# TDA5051A_DC_LC_PLCModem.net
KiCad netlist of a schematic drawn in EAGLE
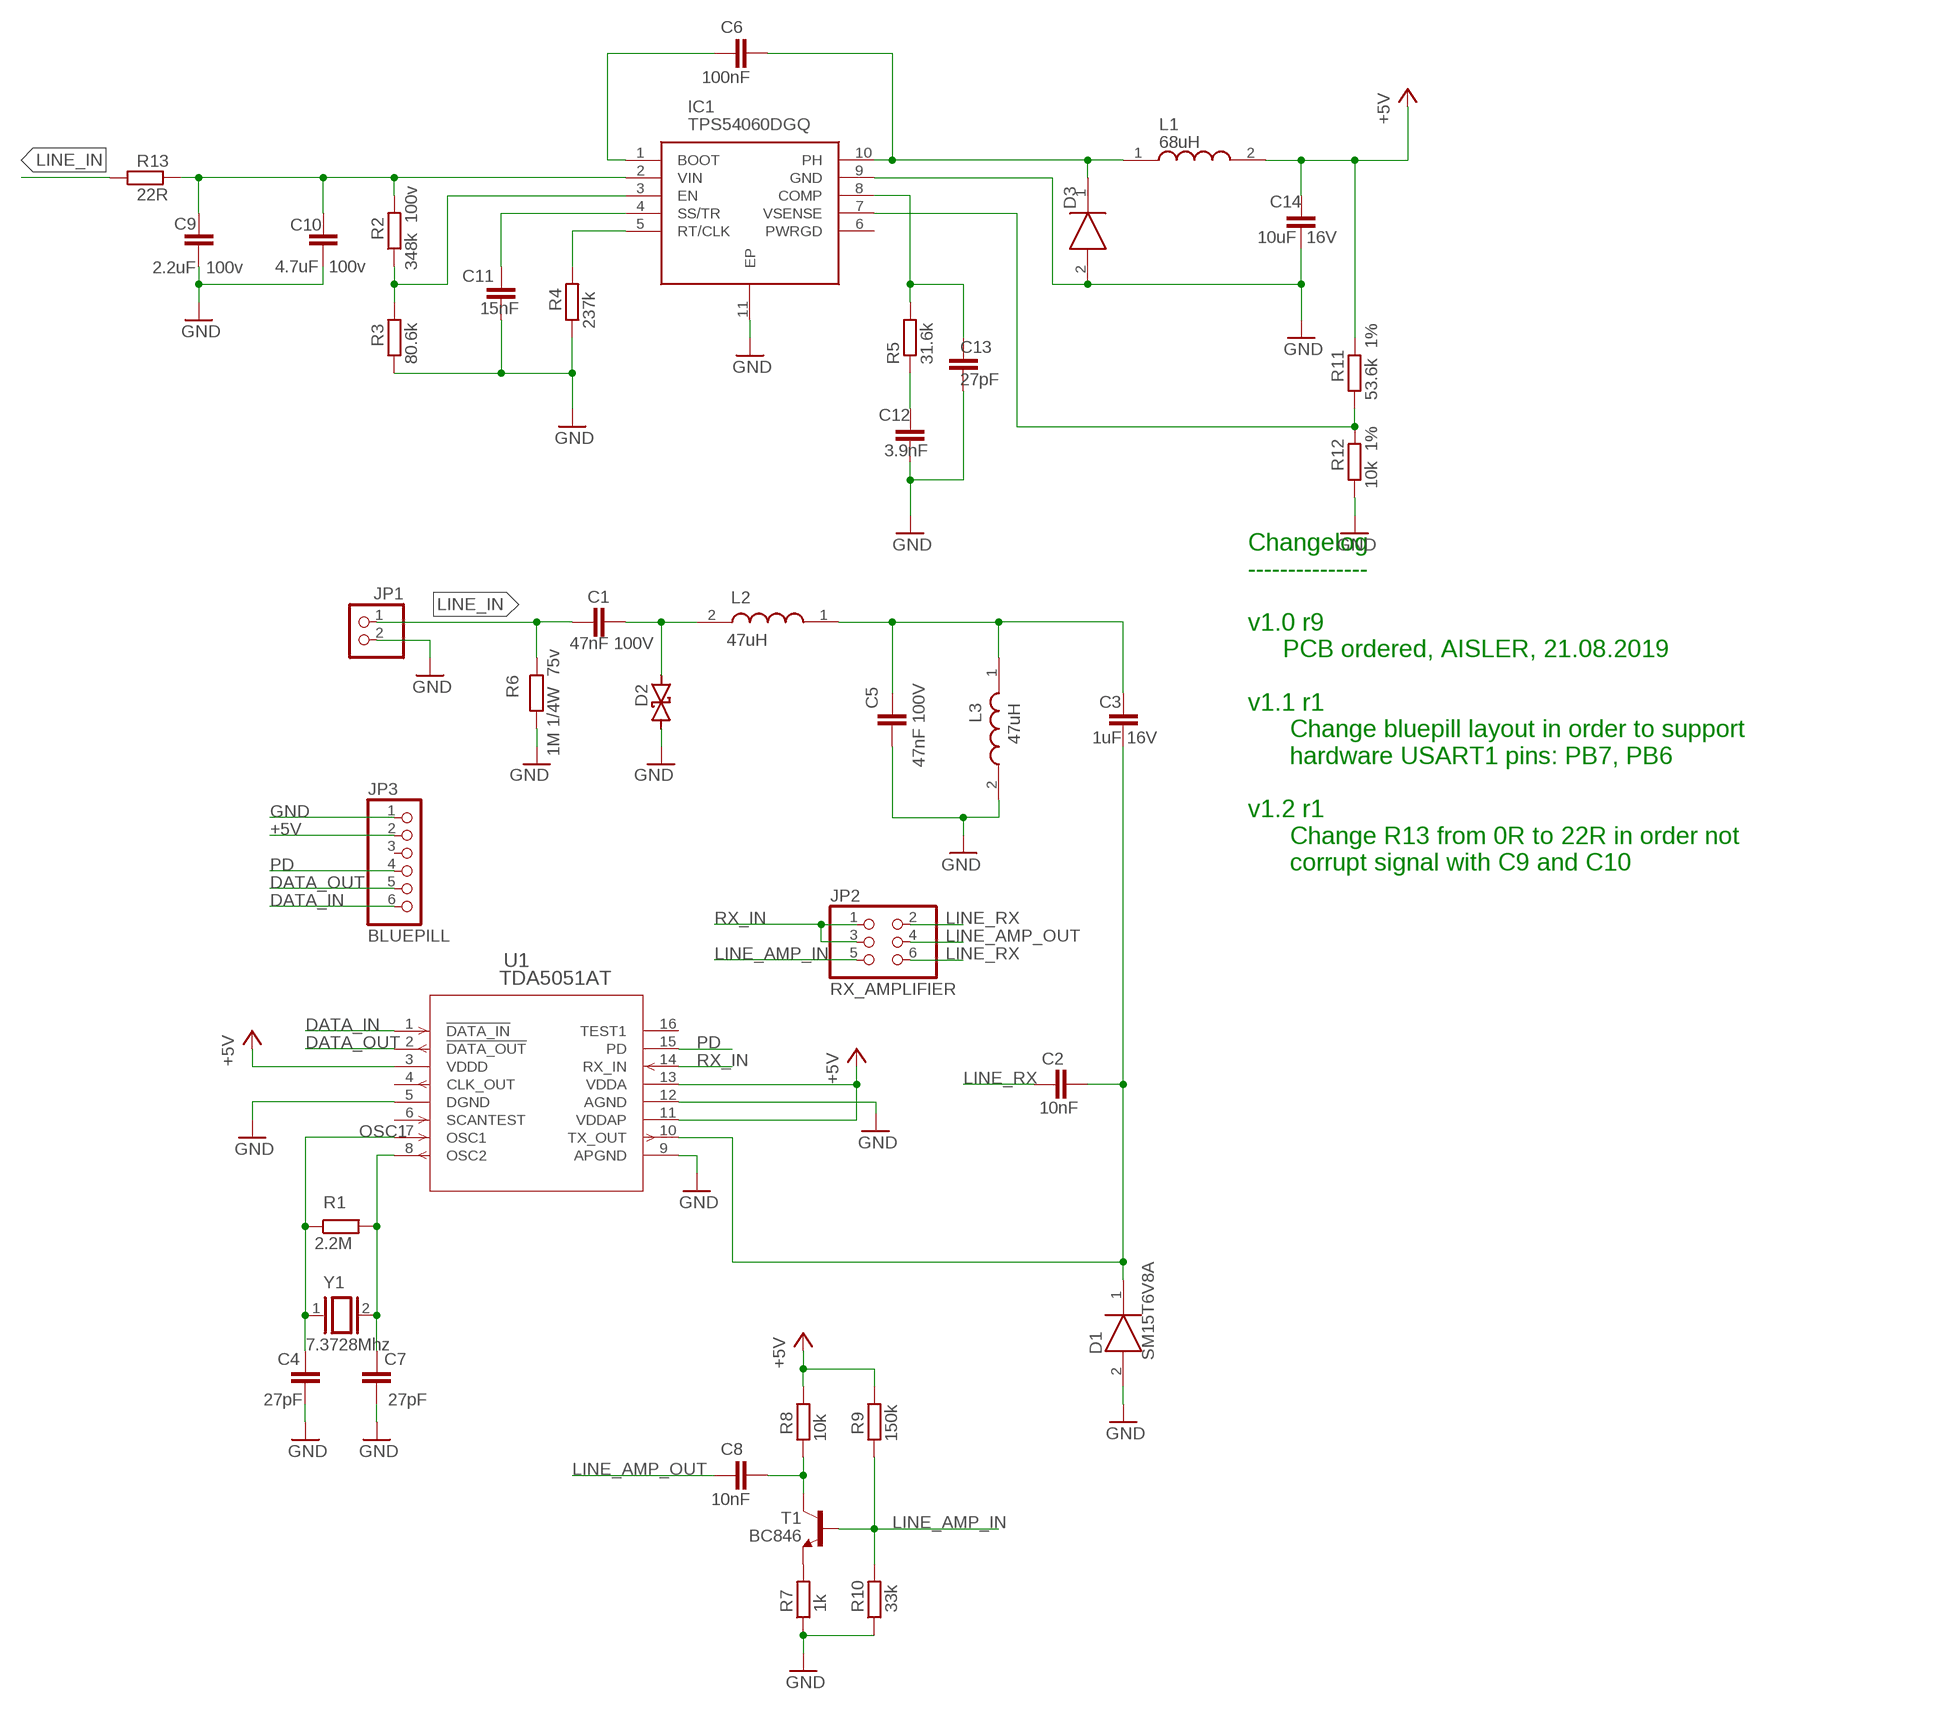
[diagram p0: schematic, sheet 1]

(export (version "E")
  (design (tool "Eeschema 10.0.6"))
  (components
    (comp (ref "C1")
      (value "47nF 100V")
      (footprint "eagle-import:C1206")
      (fields (field (name "MF") "KEMET") (field (name "MPN") "C1206C473K1RACAUTO"))
      (libsource (lib "eagle-import") (part "C-EUC1206"))
    )
    (comp (ref "C2")
      (value "10nF")
      (footprint "eagle-import:C0603")
      (fields (field (name "MF") "KEMET") (field (name "MPN") "C0603C103K5RACAUTO7411"))
      (libsource (lib "eagle-import") (part "C-EUC0603"))
    )
    (comp (ref "C3")
      (value "1uF 16V")
      (footprint "eagle-import:C0805")
      (fields (field (name "MF") "KEMET") (field (name "MPN") "C0805C105K4RACAUTO"))
      (libsource (lib "eagle-import") (part "C-EUC0805"))
    )
    (comp (ref "C4")
      (value "27pF")
      (footprint "eagle-import:C0603")
      (fields (field (name "MF") "AVX") (field (name "MPN") "06035A270JAT2A"))
      (libsource (lib "eagle-import") (part "C-EUC0603"))
    )
    (comp (ref "C5")
      (value "47nF 100V")
      (footprint "eagle-import:C1206")
      (fields (field (name "MF") "KEMET") (field (name "MPN") "C1206C473K1RACAUTO"))
      (libsource (lib "eagle-import") (part "C-EUC1206"))
    )
    (comp (ref "C6")
      (value "100nF")
      (footprint "eagle-import:C0603")
      (fields (field (name "MF") "KEMET") (field (name "MPN") "C0603C104K5RECAUTO"))
      (libsource (lib "eagle-import") (part "C-EUC0603"))
    )
    (comp (ref "C7")
      (value "27pF")
      (footprint "eagle-import:C0603")
      (fields (field (name "MF") "AVX") (field (name "MPN") "06035A270JAT2A"))
      (libsource (lib "eagle-import") (part "C-EUC0603"))
    )
    (comp (ref "C8")
      (value "10nF")
      (footprint "eagle-import:C0603")
      (fields (field (name "MF") "KEMET") (field (name "MPN") "C0603C103K5RACAUTO7411"))
      (libsource (lib "eagle-import") (part "C-EUC0603"))
    )
    (comp (ref "C9")
      (value "2.2uF 100v")
      (footprint "eagle-import:C1210")
      (fields (field (name "MF") "TDK") (field (name "MPN") "C3225X7R2A225K230AB"))
      (libsource (lib "eagle-import") (part "C-EUC1210"))
    )
    (comp (ref "C10")
      (value "4.7uF 100v")
      (footprint "eagle-import:C1210")
      (fields (field (name "MF") "TDK") (field (name "MPN") "CGA6M3X7S2A475K200AB"))
      (libsource (lib "eagle-import") (part "C-EUC1210"))
    )
    (comp (ref "C11")
      (value "15nF")
      (footprint "eagle-import:C0603")
      (fields (field (name "MF") "AVX") (field (name "MPN") "06035C153KAT2A"))
      (libsource (lib "eagle-import") (part "C-EUC0603"))
    )
    (comp (ref "C12")
      (value "3.9nF")
      (footprint "eagle-import:C0603")
      (fields (field (name "MF") "Murata Electronics") (field (name "MPN") "GCM1885C1H392JA16D"))
      (libsource (lib "eagle-import") (part "C-EUC0603"))
    )
    (comp (ref "C13")
      (value "27pF")
      (footprint "eagle-import:C0603")
      (fields (field (name "MF") "AVX") (field (name "MPN") "06035A270JAT2A"))
      (libsource (lib "eagle-import") (part "C-EUC0603"))
    )
    (comp (ref "C14")
      (value "10uF 16V")
      (footprint "eagle-import:C0603")
      (fields (field (name "MF") "Murata Electronics") (field (name "MPN") "GRM188R61C106KAALD"))
      (libsource (lib "eagle-import") (part "C-EUC0603"))
    )
    (comp (ref "D1")
      (value "SM15T6V8A")
      (footprint "eagle-import:DIOM8059X265N")
      (fields (field (name "MOUSER_PART_NUMBER") "511-SM15T6V8A") (field (name "MF") "STMicroelectronics"))
      (libsource (lib "eagle-import") (part "SM15T6V8A"))
    )
    (comp (ref "D2")
      (value "SM15T6V8CA")
      (footprint "eagle-import:DIOM8059X265N")
      (fields (field (name "MOUSER_PART_NUMBER") "511-SM15T6V8CA") (field (name "MF") "STMicroelectronics"))
      (libsource (lib "eagle-import") (part "SM15T6V8CA"))
    )
    (comp (ref "D3")
      (value "STPS2H100A")
      (footprint "eagle-import:DIOM5126X265N")
      (fields (field (name "MOUSER_PART_NUMBER") "511-STPS2H100A") (field (name "MF") "STMicroelectronics"))
      (libsource (lib "eagle-import") (part "STPS2H100A"))
    )
    (comp (ref "IC1")
      (value "TPS54060DGQ")
      (footprint "eagle-import:SOP50P490X110-11N")
      (fields
        (field (name "MOUSER_PART_NUMBER") "595-TPS54060DGQ")
        (field (name "MF") "Texas Instruments")
        (field (name "MPN") "TPS54060DGQR")
      )
      (libsource (lib "eagle-import") (part "TPS54060DGQ"))
    )
    (comp (ref "JP1")
      (value "PINHD-1X2")
      (footprint "eagle-import:1X02")
      (libsource (lib "eagle-import") (part "PINHD-1X2"))
    )
    (comp (ref "JP2")
      (value "RX_AMPLIFIER")
      (footprint "eagle-import:2X03")
      (libsource (lib "eagle-import") (part "PINHD-2X3"))
    )
    (comp (ref "JP3")
      (value "BLUEPILL")
      (footprint "eagle-import:1X06")
      (fields (field (name "MF") "Harwin") (field (name "MPN") "M20-7820646"))
      (libsource (lib "eagle-import") (part "PINHD-1X6"))
    )
    (comp (ref "L1")
      (value "68uH")
      (footprint "eagle-import:SDR0805-680KL")
      (fields
        (field (name "MANUFACTURER_PART_NUMBER") "SDR0805-680KL")
        (field (name "MOUSER_PART_NUMBER") "652-SDR0805-680KL")
        (field (name "MF") "Bourns")
      )
      (libsource (lib "eagle-import") (part "SDR0805-680KL"))
    )
    (comp (ref "L2")
      (value "47uH")
      (footprint "eagle-import:SDR1307-220ML")
      (description "BOURNS - SDR1307A-470K - INDUCTOR, 47UH, 10%, 4.2A, SMD")
      (fields
        (field (name "MANUFACTURER_PART_NUMBER") "SDR1307-470KL")
        (field (name "MOUSER_PART_NUMBER") "652-SDR1307-470KL")
        (field (name "MANUFACTURER_PART_NUMBER_1") "SDR1307A-470K")
        (field (name "MF") "Bourns")
        (field (name "MOUSER_PART_NUMBER_1") "652-SDR1307A-470K")
        (field (name "MOUSER_PRICE-STOCK") "https://www.mouser.com/Search/Refine.aspx?Keyword=652-SDR1307A-470K")
      )
      (libsource (lib "eagle-import") (part "SDR1307-470KL"))
    )
    (comp (ref "L3")
      (value "47uH")
      (footprint "eagle-import:SDR1307-220ML")
      (description "BOURNS - SDR1307A-470K - INDUCTOR, 47UH, 10%, 4.2A, SMD")
      (fields
        (field (name "MANUFACTURER_PART_NUMBER") "SDR1307-470KL")
        (field (name "MOUSER_PART_NUMBER") "652-SDR1307-470KL")
        (field (name "MANUFACTURER_PART_NUMBER_1") "SDR1307A-470K")
        (field (name "MF") "Bourns")
        (field (name "MOUSER_PART_NUMBER_1") "652-SDR1307A-470K")
        (field (name "MOUSER_PRICE-STOCK") "https://www.mouser.com/Search/Refine.aspx?Keyword=652-SDR1307A-470K")
        (field (name "SPICEPREFIX") "L")
      )
      (libsource (lib "eagle-import") (part "SDR1307-470KL"))
    )
    (comp (ref "R1")
      (value "2.2M")
      (footprint "eagle-import:R0603")
      (fields (field (name "MF") "Yageo") (field (name "MPN") "RC0603JR-072M2L"))
      (libsource (lib "eagle-import") (part "R-EU_R0603"))
    )
    (comp (ref "R2")
      (value "348k 100v")
      (footprint "eagle-import:R0603")
      (fields (field (name "MF") "Susumu") (field (name "MPN") "RG1608P-3483-D-T5"))
      (libsource (lib "eagle-import") (part "R-EU_R0603"))
    )
    (comp (ref "R3")
      (value "80.6k")
      (footprint "eagle-import:R0603")
      (fields (field (name "MF") "Vishay / Dale") (field (name "MPN") "CRCW060380K6FKEA"))
      (libsource (lib "eagle-import") (part "R-EU_R0603"))
    )
    (comp (ref "R4")
      (value "237k")
      (footprint "eagle-import:R0603")
      (fields (field (name "MF") "Yageo") (field (name "MPN") "AC0603FR-07237KL"))
      (libsource (lib "eagle-import") (part "R-EU_R0603"))
    )
    (comp (ref "R5")
      (value "31.6k")
      (footprint "eagle-import:R0603")
      (fields (field (name "MF") "Yageo") (field (name "MPN") "AC0603FR-0731K6L"))
      (libsource (lib "eagle-import") (part "R-EU_R0603"))
    )
    (comp (ref "R6")
      (value "1M 1/4W 75v")
      (footprint "eagle-import:R0603")
      (fields (field (name "MF") "Vishay / Dale") (field (name "MPN") "RCS06031M00FKEA"))
      (libsource (lib "eagle-import") (part "R-EU_R0603"))
    )
    (comp (ref "R7")
      (value "1k")
      (footprint "eagle-import:R0603")
      (fields (field (name "MF") "Vishay / Dale") (field (name "MPN") "CRCW06031K00FKEAC"))
      (libsource (lib "eagle-import") (part "R-EU_R0603"))
    )
    (comp (ref "R8")
      (value "10k")
      (footprint "eagle-import:R0603")
      (fields (field (name "MF") "Vishay / Dale") (field (name "MPN") "CRCW060310K0FKEAC"))
      (libsource (lib "eagle-import") (part "R-EU_R0603"))
    )
    (comp (ref "R9")
      (value "150k")
      (footprint "eagle-import:R0603")
      (fields (field (name "MF") "Yageo") (field (name "MPN") "RC0603FR-07150KL"))
      (libsource (lib "eagle-import") (part "R-EU_R0603"))
    )
    (comp (ref "R10")
      (value "33k")
      (footprint "eagle-import:R0603")
      (fields (field (name "MF") "Yageo") (field (name "MPN") "RC0603FR-0733KL"))
      (libsource (lib "eagle-import") (part "R-EU_R0603"))
    )
    (comp (ref "R11")
      (value "53.6k 1%")
      (footprint "eagle-import:R0603")
      (fields (field (name "MF") "Yageo") (field (name "MPN") "RC0603FR-0753K6L"))
      (libsource (lib "eagle-import") (part "R-EU_R0603"))
    )
    (comp (ref "R12")
      (value "10k 1%")
      (footprint "eagle-import:R0603")
      (fields (field (name "MF") "Vishay / Dale") (field (name "MPN") "CRCW060310K0FKEAC"))
      (libsource (lib "eagle-import") (part "R-EU_R0603"))
    )
    (comp (ref "R13")
      (value "22R")
      (footprint "eagle-import:R0603")
      (fields (field (name "MF") "Yageo") (field (name "MPN") "RC0603JR-070RL"))
      (libsource (lib "eagle-import") (part "R-EU_R0603"))
    )
    (comp (ref "T1")
      (value "BC846")
      (footprint "eagle-import:SOT23")
      (fields
        (field (name "MF") "ON Semiconductor")
        (field (name "MPN") "BC846BLT1G")
        (field (name "SPICEPREFIX") "J")
      )
      (libsource (lib "eagle-import") (part "BC846"))
    )
    (comp (ref "U1")
      (value "TDA5051AT")
      (footprint "eagle-import:SOT162-1")
      (fields (field (name "MF") "NXP Semiconductors") (field (name "MPN") "TDA5051AT/C1,518"))
      (libsource (lib "eagle-import") (part "TDA5051AT"))
    )
    (comp (ref "Y1")
      (value "7.3728Mhz")
      (footprint "eagle-import:HC_49US_(AT49)")
      (fields
        (field (name "MANUFACTURER_PART_NUMBER") "ABLS-7.3728MHZ-B2-T")
        (field (name "MOUSER_PART_NUMBER") "815-ABLS-7.3728-B2")
        (field (name "MF") "ABRACON")
      )
      (libsource (lib "eagle-import") (part "ABLS-7.3728MHZ-B2-T"))
    )
  )
  (nets
    (net (code "1") (name "+5V") (class "Default")
      (node (ref "C14") (pin "1") (pinfunction "1_1") (pintype "passive"))
      (node (ref "JP3") (pin "2") (pinfunction "2_2") (pintype "passive"))
      (node (ref "L1") (pin "2") (pinfunction "2_2") (pintype "bidirectional"))
      (node (ref "R11") (pin "2") (pinfunction "2_2") (pintype "passive"))
      (node (ref "R8") (pin "2") (pinfunction "2_2") (pintype "passive"))
      (node (ref "R9") (pin "2") (pinfunction "2_2") (pintype "passive"))
      (node (ref "U1") (pin "11") (pinfunction "VDDAP_11") (pintype "power_in"))
      (node (ref "U1") (pin "13") (pinfunction "VDDA_13") (pintype "power_in"))
      (node (ref "U1") (pin "3") (pinfunction "VDDD_3") (pintype "power_in"))
    )
    (net (code "2") (name "/DATA_IN") (class "Default")
      (node (ref "JP3") (pin "6") (pinfunction "6_6") (pintype "passive"))
      (node (ref "U1") (pin "1") (pinfunction "~{DATA_IN}_1") (pintype "input"))
    )
    (net (code "3") (name "/DATA_OUT") (class "Default")
      (node (ref "JP3") (pin "5") (pinfunction "5_5") (pintype "passive"))
      (node (ref "U1") (pin "2") (pinfunction "~{DATA_OUT}_2") (pintype "output"))
    )
    (net (code "4") (name "/LINE_AMP_IN") (class "Default")
      (node (ref "JP2") (pin "5") (pinfunction "5_5") (pintype "passive"))
      (node (ref "R10") (pin "2") (pinfunction "2_2") (pintype "passive"))
      (node (ref "R9") (pin "1") (pinfunction "1_1") (pintype "passive"))
      (node (ref "T1") (pin "1") (pinfunction "B_1") (pintype "passive"))
    )
    (net (code "5") (name "/LINE_AMP_OUT") (class "Default")
      (node (ref "C8") (pin "1") (pinfunction "1_1") (pintype "passive"))
      (node (ref "JP2") (pin "4") (pinfunction "4_4") (pintype "passive"))
    )
    (net (code "6") (name "/LINE_RX") (class "Default")
      (node (ref "C2") (pin "1") (pinfunction "1_1") (pintype "passive"))
      (node (ref "JP2") (pin "2") (pinfunction "2_2") (pintype "passive"))
      (node (ref "JP2") (pin "6") (pinfunction "6_6") (pintype "passive"))
    )
    (net (code "7") (name "/OSC1") (class "Default")
      (node (ref "C4") (pin "2") (pinfunction "2_2") (pintype "passive"))
      (node (ref "R1") (pin "1") (pinfunction "1_1") (pintype "passive"))
      (node (ref "U1") (pin "7") (pinfunction "OSC1_7") (pintype "input"))
      (node (ref "Y1") (pin "1") (pinfunction "1_1") (pintype "passive"))
    )
    (net (code "8") (name "/PD") (class "Default")
      (node (ref "JP3") (pin "4") (pinfunction "4_4") (pintype "passive"))
      (node (ref "U1") (pin "15") (pinfunction "PD_15") (pintype "power_in"))
    )
    (net (code "9") (name "/RX_IN") (class "Default")
      (node (ref "JP2") (pin "1") (pinfunction "1_1") (pintype "passive"))
      (node (ref "JP2") (pin "3") (pinfunction "3_3") (pintype "passive"))
      (node (ref "U1") (pin "14") (pinfunction "RX_IN_14") (pintype "input"))
    )
    (net (code "10") (name "/TEST1") (class "Default")
      (node (ref "U1") (pin "16") (pinfunction "TEST1_16") (pintype "power_in"))
    )
    (net (code "11") (name "GND") (class "Default")
      (node (ref "C10") (pin "2") (pinfunction "2_2") (pintype "passive"))
      (node (ref "C11") (pin "2") (pinfunction "2_2") (pintype "passive"))
      (node (ref "C12") (pin "2") (pinfunction "2_2") (pintype "passive"))
      (node (ref "C13") (pin "2") (pinfunction "2_2") (pintype "passive"))
      (node (ref "C14") (pin "2") (pinfunction "2_2") (pintype "passive"))
      (node (ref "C4") (pin "1") (pinfunction "1_1") (pintype "passive"))
      (node (ref "C5") (pin "1") (pinfunction "1_1") (pintype "passive"))
      (node (ref "C7") (pin "1") (pinfunction "1_1") (pintype "passive"))
      (node (ref "C9") (pin "2") (pinfunction "2_2") (pintype "passive"))
      (node (ref "D1") (pin "2") (pinfunction "A_2") (pintype "bidirectional"))
      (node (ref "D2") (pin "2") (pinfunction "2_2") (pintype "passive"))
      (node (ref "D3") (pin "2") (pinfunction "A_2") (pintype "bidirectional"))
      (node (ref "IC1") (pin "11") (pinfunction "EP_11") (pintype "power_in"))
      (node (ref "IC1") (pin "9") (pinfunction "GND_9") (pintype "power_in"))
      (node (ref "JP1") (pin "2") (pinfunction "2_2") (pintype "passive"))
      (node (ref "JP3") (pin "1") (pinfunction "1_1") (pintype "passive"))
      (node (ref "L3") (pin "2") (pinfunction "2_2") (pintype "bidirectional"))
      (node (ref "R10") (pin "1") (pinfunction "1_1") (pintype "passive"))
      (node (ref "R12") (pin "1") (pinfunction "1_1") (pintype "passive"))
      (node (ref "R3") (pin "1") (pinfunction "1_1") (pintype "passive"))
      (node (ref "R4") (pin "1") (pinfunction "1_1") (pintype "passive"))
      (node (ref "R6") (pin "2") (pinfunction "2_2") (pintype "passive"))
      (node (ref "R7") (pin "1") (pinfunction "1_1") (pintype "passive"))
      (node (ref "U1") (pin "12") (pinfunction "AGND_12") (pintype "power_in"))
      (node (ref "U1") (pin "5") (pinfunction "DGND_5") (pintype "power_in"))
      (node (ref "U1") (pin "9") (pinfunction "APGND_9") (pintype "power_in"))
    )
    (net (code "12") (name "LINE_IN") (class "Default")
      (node (ref "C1") (pin "1") (pinfunction "1_1") (pintype "passive"))
      (node (ref "JP1") (pin "1") (pinfunction "1_1") (pintype "passive"))
      (node (ref "R13") (pin "1") (pinfunction "1_1") (pintype "passive"))
      (node (ref "R6") (pin "1") (pinfunction "1_1") (pintype "passive"))
    )
    (net (code "13") (name "Net-(C1-Pad2)") (class "Default")
      (node (ref "C1") (pin "2") (pinfunction "2_2") (pintype "passive"))
      (node (ref "D2") (pin "1") (pinfunction "1_1") (pintype "passive"))
      (node (ref "L2") (pin "2") (pinfunction "2_2") (pintype "bidirectional"))
    )
    (net (code "14") (name "Net-(C3-Pad1)") (class "Default")
      (node (ref "C3") (pin "1") (pinfunction "1_1") (pintype "passive"))
      (node (ref "C5") (pin "2") (pinfunction "2_2") (pintype "passive"))
      (node (ref "L2") (pin "1") (pinfunction "1_1") (pintype "bidirectional"))
      (node (ref "L3") (pin "1") (pinfunction "1_1") (pintype "bidirectional"))
    )
    (net (code "15") (name "Net-(C12-Pad1)") (class "Default")
      (node (ref "C12") (pin "1") (pinfunction "1_1") (pintype "passive"))
      (node (ref "R5") (pin "1") (pinfunction "1_1") (pintype "passive"))
    )
    (net (code "16") (name "Net-(D1-K)") (class "Default")
      (node (ref "C2") (pin "2") (pinfunction "2_2") (pintype "passive"))
      (node (ref "C3") (pin "2") (pinfunction "2_2") (pintype "passive"))
      (node (ref "D1") (pin "1") (pinfunction "K_1") (pintype "bidirectional"))
      (node (ref "U1") (pin "10") (pinfunction "TX_OUT_10") (pintype "output"))
    )
    (net (code "17") (name "Net-(D3-K)") (class "Default")
      (node (ref "C6") (pin "2") (pinfunction "2_2") (pintype "passive"))
      (node (ref "D3") (pin "1") (pinfunction "K_1") (pintype "bidirectional"))
      (node (ref "IC1") (pin "10") (pinfunction "PH_10") (pintype "bidirectional"))
      (node (ref "L1") (pin "1") (pinfunction "1_1") (pintype "bidirectional"))
    )
    (net (code "18") (name "Net-(IC1-BOOT)") (class "Default")
      (node (ref "C6") (pin "1") (pinfunction "1_1") (pintype "passive"))
      (node (ref "IC1") (pin "1") (pinfunction "BOOT_1") (pintype "bidirectional"))
    )
    (net (code "19") (name "Net-(IC1-COMP)") (class "Default")
      (node (ref "C13") (pin "1") (pinfunction "1_1") (pintype "passive"))
      (node (ref "IC1") (pin "8") (pinfunction "COMP_8") (pintype "bidirectional"))
      (node (ref "R5") (pin "2") (pinfunction "2_2") (pintype "passive"))
    )
    (net (code "20") (name "Net-(IC1-EN)") (class "Default")
      (node (ref "IC1") (pin "3") (pinfunction "EN_3") (pintype "bidirectional"))
      (node (ref "R2") (pin "1") (pinfunction "1_1") (pintype "passive"))
      (node (ref "R3") (pin "2") (pinfunction "2_2") (pintype "passive"))
    )
    (net (code "21") (name "Net-(IC1-RT{slash}CLK)") (class "Default")
      (node (ref "IC1") (pin "5") (pinfunction "RT/CLK_5") (pintype "input"))
      (node (ref "R4") (pin "2") (pinfunction "2_2") (pintype "passive"))
    )
    (net (code "22") (name "Net-(IC1-SS{slash}TR)") (class "Default")
      (node (ref "C11") (pin "1") (pinfunction "1_1") (pintype "passive"))
      (node (ref "IC1") (pin "4") (pinfunction "SS/TR_4") (pintype "bidirectional"))
    )
    (net (code "23") (name "Net-(IC1-VIN)") (class "Default")
      (node (ref "C10") (pin "1") (pinfunction "1_1") (pintype "passive"))
      (node (ref "C9") (pin "1") (pinfunction "1_1") (pintype "passive"))
      (node (ref "IC1") (pin "2") (pinfunction "VIN_2") (pintype "input"))
      (node (ref "R13") (pin "2") (pinfunction "2_2") (pintype "passive"))
      (node (ref "R2") (pin "2") (pinfunction "2_2") (pintype "passive"))
    )
    (net (code "24") (name "Net-(IC1-VSENSE)") (class "Default")
      (node (ref "IC1") (pin "7") (pinfunction "VSENSE_7") (pintype "bidirectional"))
      (node (ref "R11") (pin "1") (pinfunction "1_1") (pintype "passive"))
      (node (ref "R12") (pin "2") (pinfunction "2_2") (pintype "passive"))
    )
    (net (code "25") (name "Net-(T1-C)") (class "Default")
      (node (ref "C8") (pin "2") (pinfunction "2_2") (pintype "passive"))
      (node (ref "R8") (pin "1") (pinfunction "1_1") (pintype "passive"))
      (node (ref "T1") (pin "3") (pinfunction "C_3") (pintype "passive"))
    )
    (net (code "26") (name "Net-(T1-E)") (class "Default")
      (node (ref "R7") (pin "2") (pinfunction "2_2") (pintype "passive"))
      (node (ref "T1") (pin "2") (pinfunction "E_2") (pintype "passive"))
    )
    (net (code "27") (name "Net-(U1-OSC2)") (class "Default")
      (node (ref "C7") (pin "2") (pinfunction "2_2") (pintype "passive"))
      (node (ref "R1") (pin "2") (pinfunction "2_2") (pintype "passive"))
      (node (ref "U1") (pin "8") (pinfunction "OSC2_8") (pintype "output"))
      (node (ref "Y1") (pin "2") (pinfunction "2_2") (pintype "passive"))
    )
    (net (code "28") (name "unconnected-(IC1-PWRGD-Pad6)") (class "Default")
      (node (ref "IC1") (pin "6") (pinfunction "PWRGD_6") (pintype "bidirectional"))
    )
    (net (code "29") (name "unconnected-(JP3-Pad3)") (class "Default")
      (node (ref "JP3") (pin "3") (pinfunction "3_3") (pintype "passive"))
    )
    (net (code "30") (name "unconnected-(U1-CLK_OUT-Pad4)") (class "Default")
      (node (ref "U1") (pin "4") (pinfunction "CLK_OUT_4") (pintype "output"))
    )
    (net (code "31") (name "unconnected-(U1-SCANTEST-Pad6)") (class "Default")
      (node (ref "U1") (pin "6") (pinfunction "SCANTEST_6") (pintype "input"))
    )
  )
)
